# POWER_RAIL_MONITORING.net
KiCad netlist of a schematic drawn in Altium Designer
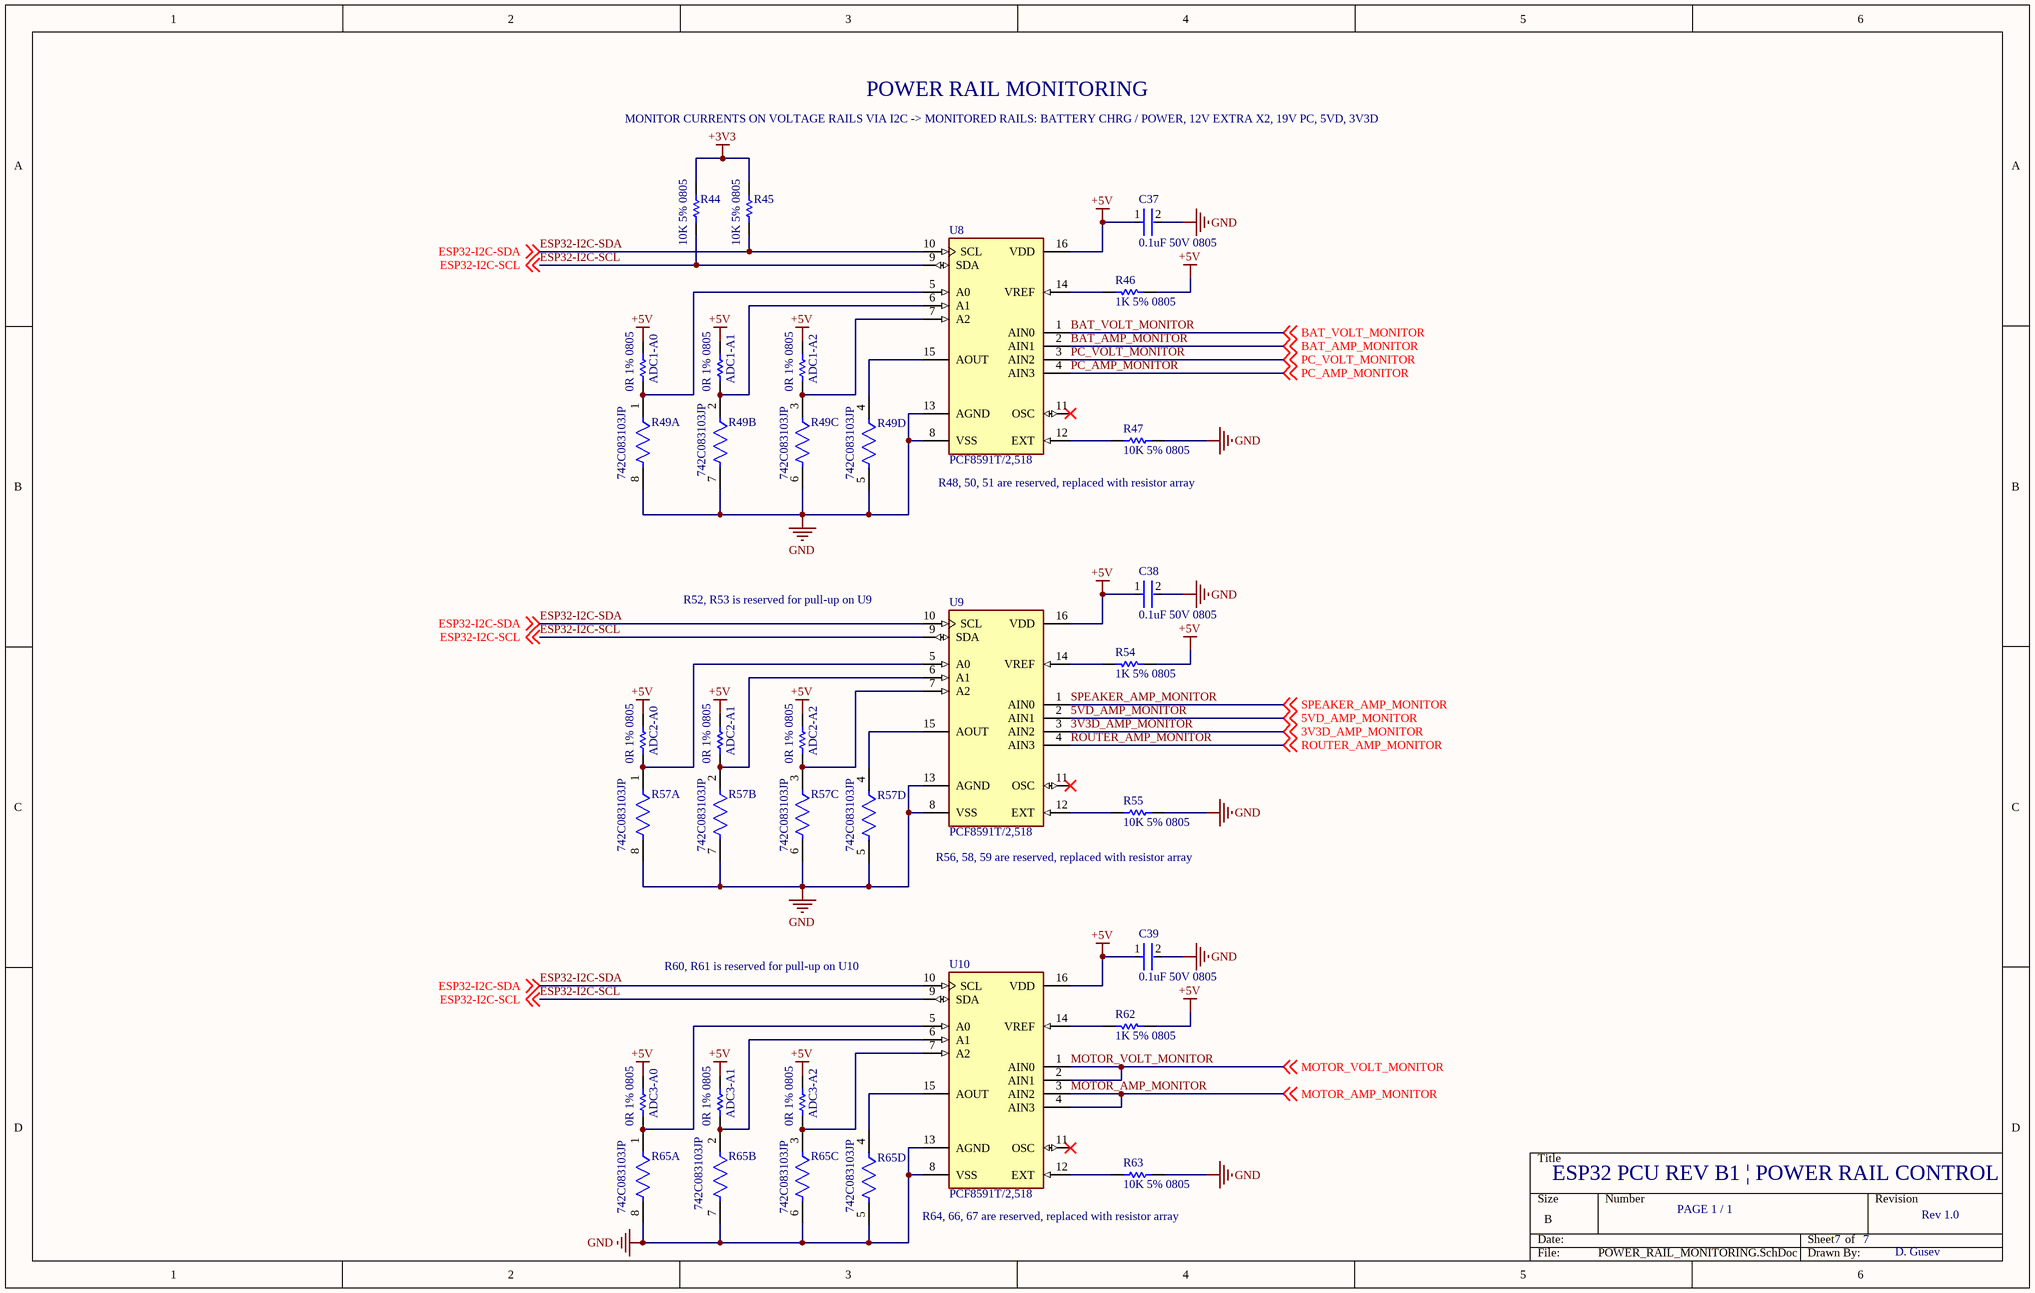
[diagram p0: POWER_RAIL_MONITORING.SchDoc]

(export (version "E")
  (design (tool "Eeschema 10.0.6"))
  (components
    (comp (ref "ADC1-A0")
      (value "0R 1% 0805")
      (footprint "RESC2013X60X35LL10T20")
      (description "Chip Resistor, 1 Ohm, +/- 1%, 125 mW, -55 to 155 degC, 0805 (2012 Metric), RoHS, Tape and Reel")
      (fields (field (name "MANUFACTURER") "Yageo"))
      (libsource (lib "Altium Content Vault") (part "RES-2"))
    )
    (comp (ref "ADC1-A1")
      (value "0R 1% 0805")
      (footprint "RESC2013X60X35LL10T20")
      (description "Chip Resistor, 1 Ohm, +/- 1%, 125 mW, -55 to 155 degC, 0805 (2012 Metric), RoHS, Tape and Reel")
      (fields (field (name "MANUFACTURER") "Yageo"))
      (libsource (lib "Altium Content Vault") (part "RES-2"))
    )
    (comp (ref "ADC1-A2")
      (value "0R 1% 0805")
      (footprint "RESC2013X60X35LL10T20")
      (description "Chip Resistor, 1 Ohm, +/- 1%, 125 mW, -55 to 155 degC, 0805 (2012 Metric), RoHS, Tape and Reel")
      (fields (field (name "MANUFACTURER") "Yageo"))
      (libsource (lib "Altium Content Vault") (part "RES-2"))
    )
    (comp (ref "ADC2-A0")
      (value "0R 1% 0805")
      (footprint "RESC2013X60X35LL10T20")
      (description "Chip Resistor, 1 Ohm, +/- 1%, 125 mW, -55 to 155 degC, 0805 (2012 Metric), RoHS, Tape and Reel")
      (fields (field (name "MANUFACTURER") "Yageo"))
      (libsource (lib "Altium Content Vault") (part "RES-2"))
    )
    (comp (ref "ADC2-A1")
      (value "0R 1% 0805")
      (footprint "RESC2013X60X35LL10T20")
      (description "Chip Resistor, 1 Ohm, +/- 1%, 125 mW, -55 to 155 degC, 0805 (2012 Metric), RoHS, Tape and Reel")
      (fields (field (name "MANUFACTURER") "Yageo"))
      (libsource (lib "Altium Content Vault") (part "RES-2"))
    )
    (comp (ref "ADC2-A2")
      (value "0R 1% 0805")
      (footprint "RESC2013X60X35LL10T20")
      (description "Chip Resistor, 1 Ohm, +/- 1%, 125 mW, -55 to 155 degC, 0805 (2012 Metric), RoHS, Tape and Reel")
      (fields (field (name "MANUFACTURER") "Yageo"))
      (libsource (lib "Altium Content Vault") (part "RES-2"))
    )
    (comp (ref "ADC3-A0")
      (value "0R 1% 0805")
      (footprint "RESC2013X60X35LL10T20")
      (description "Chip Resistor, 1 Ohm, +/- 1%, 125 mW, -55 to 155 degC, 0805 (2012 Metric), RoHS, Tape and Reel")
      (fields (field (name "MANUFACTURER") "Yageo"))
      (libsource (lib "Altium Content Vault") (part "RES-2"))
    )
    (comp (ref "ADC3-A1")
      (value "0R 1% 0805")
      (footprint "RESC2013X60X35LL10T20")
      (description "Chip Resistor, 1 Ohm, +/- 1%, 125 mW, -55 to 155 degC, 0805 (2012 Metric), RoHS, Tape and Reel")
      (fields (field (name "MANUFACTURER") "Yageo"))
      (libsource (lib "Altium Content Vault") (part "RES-2"))
    )
    (comp (ref "ADC3-A2")
      (value "0R 1% 0805")
      (footprint "RESC2013X60X35LL10T20")
      (description "Chip Resistor, 1 Ohm, +/- 1%, 125 mW, -55 to 155 degC, 0805 (2012 Metric), RoHS, Tape and Reel")
      (fields (field (name "MANUFACTURER") "Yageo"))
      (libsource (lib "Altium Content Vault") (part "RES-2"))
    )
    (comp (ref "C37")
      (value "0.1uF 50V 0805")
      (footprint "FP-C0805C-DN-MFG")
      (description "CAP CER 0.1UF 50V X7R 0805")
      (fields
        (field (name "MANUFACTURER PART NUMBER") "C0805C104K5RACTU")
        (field (name "MANUFACTURER") "KEMET")
      )
      (libsource (lib "Altium Content Vault") (part "b4654b650e69147ec39a6b967a45e02"))
    )
    (comp (ref "C38")
      (value "0.1uF 50V 0805")
      (footprint "FP-C0805C-DN-MFG")
      (description "CAP CER 0.1UF 50V X7R 0805")
      (fields
        (field (name "MANUFACTURER PART NUMBER") "C0805C104K5RACTU")
        (field (name "MANUFACTURER") "KEMET")
      )
      (libsource (lib "Altium Content Vault") (part "b4654b650e69147ec39a6b967a45e02"))
    )
    (comp (ref "C39")
      (value "0.1uF 50V 0805")
      (footprint "FP-C0805C-DN-MFG")
      (description "CAP CER 0.1UF 50V X7R 0805")
      (fields
        (field (name "MANUFACTURER PART NUMBER") "C0805C104K5RACTU")
        (field (name "MANUFACTURER") "KEMET")
      )
      (libsource (lib "Altium Content Vault") (part "b4654b650e69147ec39a6b967a45e02"))
    )
    (comp (ref "R44")
      (value "10K 5% 0805")
      (footprint "RESC2013X60X40ML20T25")
      (fields (field (name "PART NUMBER") "ERA6AEB123V") (field (name "MANUFACTURER") "Panasonic"))
      (libsource (lib "Altium Content Vault") (part "RES"))
    )
    (comp (ref "R45")
      (value "10K 5% 0805")
      (footprint "RESC2013X60X40ML20T25")
      (fields (field (name "PART NUMBER") "ERA6AEB123V") (field (name "MANUFACTURER") "Panasonic"))
      (libsource (lib "Altium Content Vault") (part "RES"))
    )
    (comp (ref "R46")
      (value "1K 5% 0805")
      (footprint "RESC2013X60X40ML20T25")
      (fields (field (name "PART NUMBER") "ERA6AEB123V") (field (name "MANUFACTURER") "Panasonic"))
      (libsource (lib "Altium Content Vault") (part "RES"))
    )
    (comp (ref "R47")
      (value "10K 5% 0805")
      (footprint "RESC2013X60X40ML20T25")
      (fields (field (name "PART NUMBER") "ERA6AEB123V") (field (name "MANUFACTURER") "Panasonic"))
      (libsource (lib "Altium Content Vault") (part "RES"))
    )
    (comp (ref "R49")
      (value "742C083103JP")
      (footprint "FP-742C083-MFG")
      (description "RES ARRAY 4 RES 10K OHM 1206")
      (fields (field (name "TOLERANCE") "5%"))
      (libsource (lib "Altium Content Vault") (part "46c0e806a6f3a765a2d55930d12d044"))
    )
    (comp (ref "R54")
      (value "1K 5% 0805")
      (footprint "RESC2013X60X40ML20T25")
      (fields (field (name "PART NUMBER") "ERA6AEB123V") (field (name "MANUFACTURER") "Panasonic"))
      (libsource (lib "Altium Content Vault") (part "RES"))
    )
    (comp (ref "R55")
      (value "10K 5% 0805")
      (footprint "RESC2013X60X40ML20T25")
      (fields (field (name "PART NUMBER") "ERA6AEB123V") (field (name "MANUFACTURER") "Panasonic"))
      (libsource (lib "Altium Content Vault") (part "RES"))
    )
    (comp (ref "R57")
      (value "742C083103JP")
      (footprint "FP-742C083-MFG")
      (description "RES ARRAY 4 RES 10K OHM 1206")
      (fields (field (name "TOLERANCE") "5%"))
      (libsource (lib "Altium Content Vault") (part "46c0e806a6f3a765a2d55930d12d044"))
    )
    (comp (ref "R62")
      (value "1K 5% 0805")
      (footprint "RESC2013X60X40ML20T25")
      (fields (field (name "PART NUMBER") "ERA6AEB123V") (field (name "MANUFACTURER") "Panasonic"))
      (libsource (lib "Altium Content Vault") (part "RES"))
    )
    (comp (ref "R63")
      (value "10K 5% 0805")
      (footprint "RESC2013X60X40ML20T25")
      (fields (field (name "PART NUMBER") "ERA6AEB123V") (field (name "MANUFACTURER") "Panasonic"))
      (libsource (lib "Altium Content Vault") (part "RES"))
    )
    (comp (ref "R65")
      (value "742C083103JP")
      (footprint "FP-742C083-MFG")
      (description "RES ARRAY 4 RES 10K OHM 1206")
      (fields (field (name "TOLERANCE") "5%"))
      (libsource (lib "Altium Content Vault") (part "46c0e806a6f3a765a2d55930d12d044"))
    )
    (comp (ref "U8")
      (value "PCF8591T/2,518")
      (footprint "FP-SOT162-1-MFG")
      (description "IC ADC/DAC 8BIT 11.1K 16SO")
      (fields
        (field (name "OCTOPART") "https://octopart.com/pcf8591t%2F2%2C518-nxp+semiconductors-7871876")
        (field (name "MANUFACTURER") "NXP Semiconductors")
      )
      (libsource (lib "Altium Content Vault") (part "ec71182d53123688252d871f2593ad3"))
    )
    (comp (ref "U9")
      (value "PCF8591T/2,518")
      (footprint "FP-SOT162-1-MFG")
      (description "IC ADC/DAC 8BIT 11.1K 16SO")
      (fields
        (field (name "OCTOPART") "https://octopart.com/pcf8591t%2F2%2C518-nxp+semiconductors-7871876")
        (field (name "MANUFACTURER") "NXP Semiconductors")
      )
      (libsource (lib "Altium Content Vault") (part "ec71182d53123688252d871f2593ad3"))
    )
    (comp (ref "U10")
      (value "PCF8591T/2,518")
      (footprint "FP-SOT162-1-MFG")
      (description "IC ADC/DAC 8BIT 11.1K 16SO")
      (fields
        (field (name "OCTOPART") "https://octopart.com/pcf8591t%2F2%2C518-nxp+semiconductors-7871876")
        (field (name "MANUFACTURER") "NXP Semiconductors")
      )
      (libsource (lib "Altium Content Vault") (part "ec71182d53123688252d871f2593ad3"))
    )
  )
  (nets
    (net (code "1") (name "+3V3") (class "Default")
      (node (ref "R44") (pin "2") (pinfunction "2_2") (pintype "passive"))
      (node (ref "R45") (pin "2") (pinfunction "2_2") (pintype "passive"))
    )
    (net (code "2") (name "+5V") (class "Default")
      (node (ref "ADC1-A0") (pin "1") (pinfunction "1_1") (pintype "passive"))
      (node (ref "ADC1-A1") (pin "1") (pinfunction "1_1") (pintype "passive"))
      (node (ref "ADC1-A2") (pin "1") (pinfunction "1_1") (pintype "passive"))
      (node (ref "ADC2-A0") (pin "1") (pinfunction "1_1") (pintype "passive"))
      (node (ref "ADC2-A1") (pin "1") (pinfunction "1_1") (pintype "passive"))
      (node (ref "ADC2-A2") (pin "1") (pinfunction "1_1") (pintype "passive"))
      (node (ref "ADC3-A0") (pin "1") (pinfunction "1_1") (pintype "passive"))
      (node (ref "ADC3-A1") (pin "1") (pinfunction "1_1") (pintype "passive"))
      (node (ref "ADC3-A2") (pin "1") (pinfunction "1_1") (pintype "passive"))
      (node (ref "C37") (pin "1") (pinfunction "1_1") (pintype "passive"))
      (node (ref "C38") (pin "1") (pinfunction "1_1") (pintype "passive"))
      (node (ref "C39") (pin "1") (pinfunction "1_1") (pintype "passive"))
      (node (ref "R46") (pin "2") (pinfunction "2_2") (pintype "passive"))
      (node (ref "R54") (pin "2") (pinfunction "2_2") (pintype "passive"))
      (node (ref "R62") (pin "2") (pinfunction "2_2") (pintype "passive"))
      (node (ref "U10") (pin "16") (pinfunction "VDD_16") (pintype "power_in"))
      (node (ref "U8") (pin "16") (pinfunction "VDD_16") (pintype "power_in"))
      (node (ref "U9") (pin "16") (pinfunction "VDD_16") (pintype "power_in"))
    )
    (net (code "3") (name "3V3D_AMP_MONITOR") (class "Default")
      (node (ref "U9") (pin "3") (pinfunction "AIN2_3") (pintype "passive"))
    )
    (net (code "4") (name "5VD_AMP_MONITOR") (class "Default")
      (node (ref "U9") (pin "2") (pinfunction "AIN1_2") (pintype "passive"))
    )
    (net (code "5") (name "BAT_AMP_MONITOR") (class "Default")
      (node (ref "U8") (pin "2") (pinfunction "AIN1_2") (pintype "passive"))
    )
    (net (code "6") (name "BAT_VOLT_MONITOR") (class "Default")
      (node (ref "U8") (pin "1") (pinfunction "AIN0_1") (pintype "passive"))
    )
    (net (code "7") (name "ESP32-I2C-SCL") (class "Default")
      (node (ref "R44") (pin "1") (pinfunction "1_1") (pintype "passive"))
      (node (ref "U10") (pin "9") (pinfunction "SDA_9") (pintype "bidirectional"))
      (node (ref "U8") (pin "9") (pinfunction "SDA_9") (pintype "bidirectional"))
      (node (ref "U9") (pin "9") (pinfunction "SDA_9") (pintype "bidirectional"))
    )
    (net (code "8") (name "ESP32-I2C-SDA") (class "Default")
      (node (ref "R45") (pin "1") (pinfunction "1_1") (pintype "passive"))
      (node (ref "U10") (pin "10") (pinfunction "SCL_10") (pintype "input"))
      (node (ref "U8") (pin "10") (pinfunction "SCL_10") (pintype "input"))
      (node (ref "U9") (pin "10") (pinfunction "SCL_10") (pintype "input"))
    )
    (net (code "9") (name "GND") (class "Default")
      (node (ref "C37") (pin "2") (pinfunction "2_2") (pintype "passive"))
      (node (ref "C38") (pin "2") (pinfunction "2_2") (pintype "passive"))
      (node (ref "C39") (pin "2") (pinfunction "2_2") (pintype "passive"))
      (node (ref "R47") (pin "2") (pinfunction "2_2") (pintype "passive"))
      (node (ref "R49") (pin "5") (pinfunction "5_5") (pintype "passive"))
      (node (ref "R49") (pin "6") (pinfunction "6_6") (pintype "passive"))
      (node (ref "R49") (pin "7") (pinfunction "7_7") (pintype "passive"))
      (node (ref "R49") (pin "8") (pinfunction "8_8") (pintype "passive"))
      (node (ref "R55") (pin "2") (pinfunction "2_2") (pintype "passive"))
      (node (ref "R57") (pin "5") (pinfunction "5_5") (pintype "passive"))
      (node (ref "R57") (pin "6") (pinfunction "6_6") (pintype "passive"))
      (node (ref "R57") (pin "7") (pinfunction "7_7") (pintype "passive"))
      (node (ref "R57") (pin "8") (pinfunction "8_8") (pintype "passive"))
      (node (ref "R63") (pin "2") (pinfunction "2_2") (pintype "passive"))
      (node (ref "R65") (pin "5") (pinfunction "5_5") (pintype "passive"))
      (node (ref "R65") (pin "6") (pinfunction "6_6") (pintype "passive"))
      (node (ref "R65") (pin "7") (pinfunction "7_7") (pintype "passive"))
      (node (ref "R65") (pin "8") (pinfunction "8_8") (pintype "passive"))
      (node (ref "U10") (pin "13") (pinfunction "AGND_13") (pintype "power_in"))
      (node (ref "U10") (pin "8") (pinfunction "VSS_8") (pintype "power_in"))
      (node (ref "U8") (pin "13") (pinfunction "AGND_13") (pintype "power_in"))
      (node (ref "U8") (pin "8") (pinfunction "VSS_8") (pintype "power_in"))
      (node (ref "U9") (pin "13") (pinfunction "AGND_13") (pintype "power_in"))
      (node (ref "U9") (pin "8") (pinfunction "VSS_8") (pintype "power_in"))
    )
    (net (code "10") (name "MOTOR_AMP_MONITOR") (class "Default")
      (node (ref "U10") (pin "3") (pinfunction "AIN2_3") (pintype "passive"))
      (node (ref "U10") (pin "4") (pinfunction "AIN3_4") (pintype "passive"))
    )
    (net (code "11") (name "MOTOR_VOLT_MONITOR") (class "Default")
      (node (ref "U10") (pin "1") (pinfunction "AIN0_1") (pintype "passive"))
      (node (ref "U10") (pin "2") (pinfunction "AIN1_2") (pintype "passive"))
    )
    (net (code "12") (name "Net-(U8-A0)") (class "Default")
      (node (ref "ADC1-A0") (pin "2") (pinfunction "2_2") (pintype "passive"))
      (node (ref "R49") (pin "1") (pinfunction "1_1") (pintype "passive"))
      (node (ref "U8") (pin "5") (pinfunction "A0_5") (pintype "input"))
    )
    (net (code "13") (name "Net-(U8-A1)") (class "Default")
      (node (ref "ADC1-A1") (pin "2") (pinfunction "2_2") (pintype "passive"))
      (node (ref "R49") (pin "2") (pinfunction "2_2") (pintype "passive"))
      (node (ref "U8") (pin "6") (pinfunction "A1_6") (pintype "input"))
    )
    (net (code "14") (name "Net-(U8-A2)") (class "Default")
      (node (ref "ADC1-A2") (pin "2") (pinfunction "2_2") (pintype "passive"))
      (node (ref "R49") (pin "3") (pinfunction "3_3") (pintype "passive"))
      (node (ref "U8") (pin "7") (pinfunction "A2_7") (pintype "input"))
    )
    (net (code "15") (name "Net-(U8-AOUT)") (class "Default")
      (node (ref "R49") (pin "4") (pinfunction "4_4") (pintype "passive"))
      (node (ref "U8") (pin "15") (pinfunction "AOUT_15") (pintype "passive"))
    )
    (net (code "16") (name "Net-(U8-EXT)") (class "Default")
      (node (ref "R47") (pin "1") (pinfunction "1_1") (pintype "passive"))
      (node (ref "U8") (pin "12") (pinfunction "EXT_12") (pintype "input"))
    )
    (net (code "17") (name "Net-(U8-VREF)") (class "Default")
      (node (ref "R46") (pin "1") (pinfunction "1_1") (pintype "passive"))
      (node (ref "U8") (pin "14") (pinfunction "VREF_14") (pintype "input"))
    )
    (net (code "18") (name "Net-(U9-A0)") (class "Default")
      (node (ref "ADC2-A0") (pin "2") (pinfunction "2_2") (pintype "passive"))
      (node (ref "R57") (pin "1") (pinfunction "1_1") (pintype "passive"))
      (node (ref "U9") (pin "5") (pinfunction "A0_5") (pintype "input"))
    )
    (net (code "19") (name "Net-(U9-A1)") (class "Default")
      (node (ref "ADC2-A1") (pin "2") (pinfunction "2_2") (pintype "passive"))
      (node (ref "R57") (pin "2") (pinfunction "2_2") (pintype "passive"))
      (node (ref "U9") (pin "6") (pinfunction "A1_6") (pintype "input"))
    )
    (net (code "20") (name "Net-(U9-A2)") (class "Default")
      (node (ref "ADC2-A2") (pin "2") (pinfunction "2_2") (pintype "passive"))
      (node (ref "R57") (pin "3") (pinfunction "3_3") (pintype "passive"))
      (node (ref "U9") (pin "7") (pinfunction "A2_7") (pintype "input"))
    )
    (net (code "21") (name "Net-(U9-AOUT)") (class "Default")
      (node (ref "R57") (pin "4") (pinfunction "4_4") (pintype "passive"))
      (node (ref "U9") (pin "15") (pinfunction "AOUT_15") (pintype "passive"))
    )
    (net (code "22") (name "Net-(U9-EXT)") (class "Default")
      (node (ref "R55") (pin "1") (pinfunction "1_1") (pintype "passive"))
      (node (ref "U9") (pin "12") (pinfunction "EXT_12") (pintype "input"))
    )
    (net (code "23") (name "Net-(U9-VREF)") (class "Default")
      (node (ref "R54") (pin "1") (pinfunction "1_1") (pintype "passive"))
      (node (ref "U9") (pin "14") (pinfunction "VREF_14") (pintype "input"))
    )
    (net (code "24") (name "Net-(U10-A0)") (class "Default")
      (node (ref "ADC3-A0") (pin "2") (pinfunction "2_2") (pintype "passive"))
      (node (ref "R65") (pin "1") (pinfunction "1_1") (pintype "passive"))
      (node (ref "U10") (pin "5") (pinfunction "A0_5") (pintype "input"))
    )
    (net (code "25") (name "Net-(U10-A1)") (class "Default")
      (node (ref "ADC3-A1") (pin "2") (pinfunction "2_2") (pintype "passive"))
      (node (ref "R65") (pin "2") (pinfunction "2_2") (pintype "passive"))
      (node (ref "U10") (pin "6") (pinfunction "A1_6") (pintype "input"))
    )
    (net (code "26") (name "Net-(U10-A2)") (class "Default")
      (node (ref "ADC3-A2") (pin "2") (pinfunction "2_2") (pintype "passive"))
      (node (ref "R65") (pin "3") (pinfunction "3_3") (pintype "passive"))
      (node (ref "U10") (pin "7") (pinfunction "A2_7") (pintype "input"))
    )
    (net (code "27") (name "Net-(U10-AOUT)") (class "Default")
      (node (ref "R65") (pin "4") (pinfunction "4_4") (pintype "passive"))
      (node (ref "U10") (pin "15") (pinfunction "AOUT_15") (pintype "passive"))
    )
    (net (code "28") (name "Net-(U10-EXT)") (class "Default")
      (node (ref "R63") (pin "1") (pinfunction "1_1") (pintype "passive"))
      (node (ref "U10") (pin "12") (pinfunction "EXT_12") (pintype "input"))
    )
    (net (code "29") (name "Net-(U10-VREF)") (class "Default")
      (node (ref "R62") (pin "1") (pinfunction "1_1") (pintype "passive"))
      (node (ref "U10") (pin "14") (pinfunction "VREF_14") (pintype "input"))
    )
    (net (code "30") (name "PC_AMP_MONITOR") (class "Default")
      (node (ref "U8") (pin "4") (pinfunction "AIN3_4") (pintype "passive"))
    )
    (net (code "31") (name "PC_VOLT_MONITOR") (class "Default")
      (node (ref "U8") (pin "3") (pinfunction "AIN2_3") (pintype "passive"))
    )
    (net (code "32") (name "ROUTER_AMP_MONITOR") (class "Default")
      (node (ref "U9") (pin "4") (pinfunction "AIN3_4") (pintype "passive"))
    )
    (net (code "33") (name "SPEAKER_AMP_MONITOR") (class "Default")
      (node (ref "U9") (pin "1") (pinfunction "AIN0_1") (pintype "passive"))
    )
    (net (code "34") (name "unconnected-(U8-OSC-Pad11)") (class "Default")
      (node (ref "U8") (pin "11") (pinfunction "OSC_11") (pintype "bidirectional+no_connect"))
    )
    (net (code "35") (name "unconnected-(U9-OSC-Pad11)") (class "Default")
      (node (ref "U9") (pin "11") (pinfunction "OSC_11") (pintype "bidirectional+no_connect"))
    )
    (net (code "36") (name "unconnected-(U10-OSC-Pad11)") (class "Default")
      (node (ref "U10") (pin "11") (pinfunction "OSC_11") (pintype "bidirectional+no_connect"))
    )
  )
)
